# A4988_to_FET_drive.net
KiCad netlist of a schematic drawn in EasyEDA
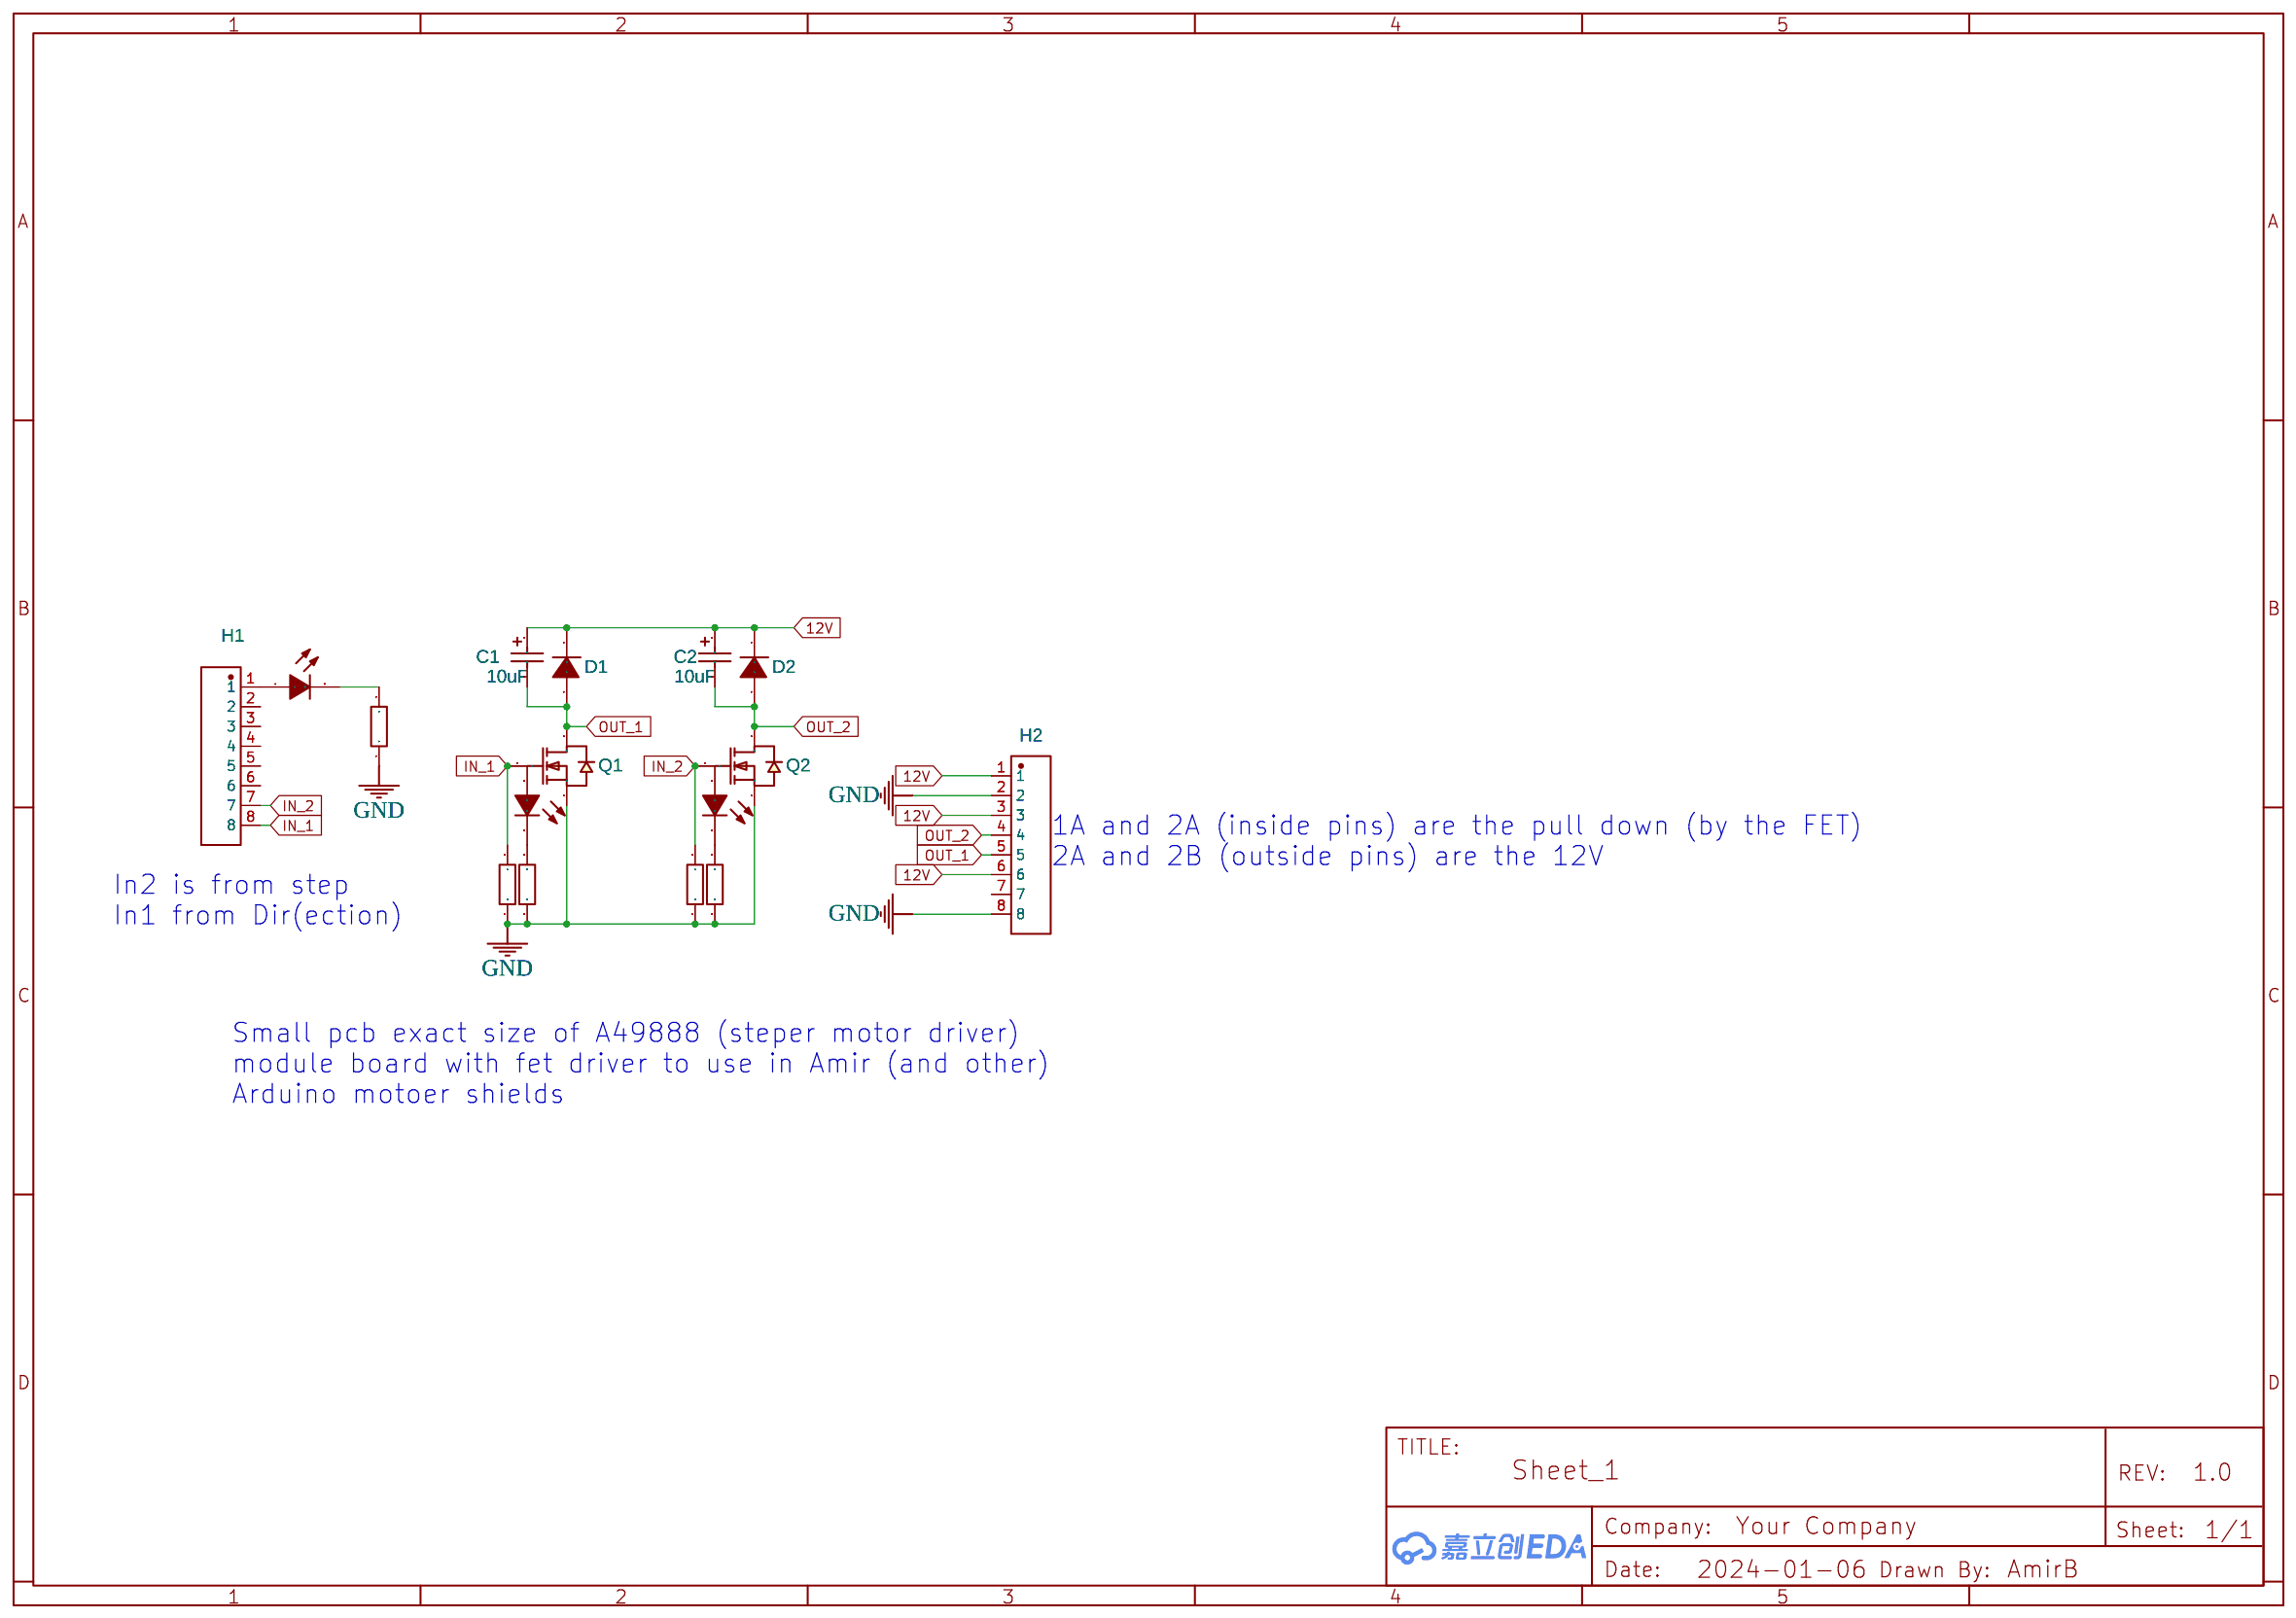
[diagram p0: schematic sheet]

(export (version "E")
  (design (tool "Eeschema 10.0.6"))
  (components
    (comp (ref "C1")
      (value "10uF")
      (fields (field (name "Manufacturer Part") "TAJA106K016RNJ") (field (name "Manufacturer") "Kyocera AVX"))
      (libsource (lib "") (part "TAJA106K016RNJ"))
    )
    (comp (ref "C2")
      (value "10uF")
      (fields (field (name "Manufacturer Part") "TAJA106K016RNJ") (field (name "Manufacturer") "Kyocera AVX"))
      (libsource (lib "") (part "TAJA106K016RNJ"))
    )
    (comp (ref "D1")
      (value "M7_C95872")
      (fields (field (name "Manufacturer Part") "M7") (field (name "Manufacturer") "MDD"))
      (libsource (lib "") (part "M7_C95872"))
    )
    (comp (ref "D2")
      (value "M7_C95872")
      (fields (field (name "Manufacturer Part") "M7") (field (name "Manufacturer") "MDD"))
      (libsource (lib "") (part "M7_C95872"))
    )
    (comp (ref "H1")
      (value "DZ254R-11-08-63")
      (fields (field (name "Manufacturer") "DEALON(德艺隆)"))
      (libsource (lib "") (part "DZ254R-11-08-63_1"))
    )
    (comp (ref "H2")
      (value "DZ254R-11-08-63")
      (fields (field (name "Manufacturer") "DEALON(德艺隆)"))
      (libsource (lib "") (part "DZ254R-11-08-63"))
    )
    (comp (ref "L1")
      (value "LED")
      (fields
        (field (name "BOM_Manufacturer Part") "19-217/BHC-ZL1M2RY/3T")
        (field (name "BOM_Supplier Part") "C72041")
      )
      (libsource (lib "") (part "19-217/BHC-ZL1M2RY/3T_1"))
    )
    (comp (ref "L2")
      (value "LED")
      (fields
        (field (name "BOM_Manufacturer Part") "19-217/BHC-ZL1M2RY/3T")
        (field (name "BOM_Supplier Part") "C72041")
      )
      (libsource (lib "") (part "19-217/BHC-ZL1M2RY/3T_1"))
    )
    (comp (ref "L3")
      (value "LED")
      (fields
        (field (name "BOM_Manufacturer Part") "19-217/BHC-ZL1M2RY/3T")
        (field (name "BOM_Supplier Part") "C72041")
      )
      (libsource (lib "") (part "19-217/BHC-ZL1M2RY/3T"))
    )
    (comp (ref "PR4")
      (value "R10K")
      (fields
        (field (name "BOM_Manufacturer Part") "0603WAF1002T5E")
        (field (name "BOM_Supplier Part") "C25804")
      )
      (libsource (lib "") (part "0603WAF1001T5E_1"))
    )
    (comp (ref "Q1")
      (value "AO3400A")
      (fields (field (name "Manufacturer") "AOS"))
      (libsource (lib "") (part "AO3400A"))
    )
    (comp (ref "Q2")
      (value "AO3400A")
      (fields (field (name "Manufacturer") "AOS"))
      (libsource (lib "") (part "AO3400A"))
    )
    (comp (ref "R2")
      (value "R10K")
      (fields
        (field (name "BOM_Manufacturer Part") "0603WAF1002T5E")
        (field (name "BOM_Supplier Part") "C25804")
      )
      (libsource (lib "") (part "0603WAF1001T5E_2"))
    )
    (comp (ref "RL1")
      (value "R10K")
      (fields
        (field (name "BOM_Manufacturer Part") "0603WAF1002T5E")
        (field (name "BOM_Supplier Part") "C25804")
      )
      (libsource (lib "") (part "0603WAF1001T5E"))
    )
    (comp (ref "RL2")
      (value "R10K")
      (fields
        (field (name "BOM_Manufacturer Part") "0603WAF1002T5E")
        (field (name "BOM_Supplier Part") "C25804")
      )
      (libsource (lib "") (part "0603WAF1001T5E"))
    )
    (comp (ref "RL3")
      (value "R10K")
      (fields
        (field (name "BOM_Manufacturer Part") "0603WAF1002T5E")
        (field (name "BOM_Supplier Part") "C25804")
      )
      (libsource (lib "") (part "0603WAF1001T5E"))
    )
  )
  (nets
    (net (code "1") (name "12V") (class "Default")
      (node (ref "C1") (pin "1") (pinfunction "1_1") (pintype "input"))
      (node (ref "C2") (pin "1") (pinfunction "1_1") (pintype "input"))
      (node (ref "D1") (pin "1") (pinfunction "K_1") (pintype "unspecified"))
      (node (ref "D2") (pin "1") (pinfunction "K_1") (pintype "unspecified"))
      (node (ref "H2") (pin "1") (pinfunction "1_1") (pintype "unspecified"))
      (node (ref "H2") (pin "3") (pinfunction "3_3") (pintype "unspecified"))
      (node (ref "H2") (pin "6") (pinfunction "6_6") (pintype "unspecified"))
    )
    (net (code "2") (name "GND") (class "Default")
      (node (ref "H2") (pin "2") (pinfunction "2_2") (pintype "unspecified"))
      (node (ref "H2") (pin "8") (pinfunction "8_8") (pintype "unspecified"))
      (node (ref "PR4") (pin "1") (pinfunction "1_1") (pintype "input"))
      (node (ref "Q1") (pin "2") (pinfunction "S_2") (pintype "unspecified"))
      (node (ref "Q2") (pin "2") (pinfunction "S_2") (pintype "unspecified"))
      (node (ref "R2") (pin "1") (pinfunction "1_1") (pintype "input"))
      (node (ref "RL1") (pin "1") (pinfunction "1_1") (pintype "input"))
      (node (ref "RL2") (pin "1") (pinfunction "1_1") (pintype "input"))
      (node (ref "RL3") (pin "1") (pinfunction "1_1") (pintype "input"))
    )
    (net (code "3") (name "IN_1") (class "Default")
      (node (ref "H1") (pin "8") (pinfunction "8_8") (pintype "unspecified"))
      (node (ref "L1") (pin "1") (pinfunction "A_1") (pintype "input"))
      (node (ref "PR4") (pin "2") (pinfunction "2_2") (pintype "input"))
      (node (ref "Q1") (pin "1") (pinfunction "G_1") (pintype "unspecified"))
    )
    (net (code "4") (name "IN_2") (class "Default")
      (node (ref "H1") (pin "7") (pinfunction "7_7") (pintype "unspecified"))
      (node (ref "L2") (pin "1") (pinfunction "A_1") (pintype "input"))
      (node (ref "Q2") (pin "1") (pinfunction "G_1") (pintype "unspecified"))
      (node (ref "R2") (pin "2") (pinfunction "2_2") (pintype "input"))
    )
    (net (code "5") (name "Net-(L1-C)") (class "Default")
      (node (ref "L1") (pin "2") (pinfunction "C_2") (pintype "input"))
      (node (ref "RL1") (pin "2") (pinfunction "2_2") (pintype "input"))
    )
    (net (code "6") (name "Net-(L2-C)") (class "Default")
      (node (ref "L2") (pin "2") (pinfunction "C_2") (pintype "input"))
      (node (ref "RL2") (pin "2") (pinfunction "2_2") (pintype "input"))
    )
    (net (code "7") (name "Net-(L3-A)") (class "Default")
      (node (ref "H1") (pin "1") (pinfunction "1_1") (pintype "unspecified"))
      (node (ref "L3") (pin "1") (pinfunction "A_1") (pintype "input"))
    )
    (net (code "8") (name "Net-(L3-C)") (class "Default")
      (node (ref "L3") (pin "2") (pinfunction "C_2") (pintype "input"))
      (node (ref "RL3") (pin "2") (pinfunction "2_2") (pintype "input"))
    )
    (net (code "9") (name "OUT_1") (class "Default")
      (node (ref "C1") (pin "2") (pinfunction "2_2") (pintype "input"))
      (node (ref "D1") (pin "2") (pinfunction "A_2") (pintype "unspecified"))
      (node (ref "H2") (pin "5") (pinfunction "5_5") (pintype "unspecified"))
      (node (ref "Q1") (pin "3") (pinfunction "D_3") (pintype "unspecified"))
    )
    (net (code "10") (name "OUT_2") (class "Default")
      (node (ref "C2") (pin "2") (pinfunction "2_2") (pintype "input"))
      (node (ref "D2") (pin "2") (pinfunction "A_2") (pintype "unspecified"))
      (node (ref "H2") (pin "4") (pinfunction "4_4") (pintype "unspecified"))
      (node (ref "Q2") (pin "3") (pinfunction "D_3") (pintype "unspecified"))
    )
    (net (code "11") (name "unconnected-(H1-Pad2)") (class "Default")
      (node (ref "H1") (pin "2") (pinfunction "2_2") (pintype "unspecified"))
    )
    (net (code "12") (name "unconnected-(H1-Pad3)") (class "Default")
      (node (ref "H1") (pin "3") (pinfunction "3_3") (pintype "unspecified"))
    )
    (net (code "13") (name "unconnected-(H1-Pad4)") (class "Default")
      (node (ref "H1") (pin "4") (pinfunction "4_4") (pintype "unspecified"))
    )
    (net (code "14") (name "unconnected-(H1-Pad5)") (class "Default")
      (node (ref "H1") (pin "5") (pinfunction "5_5") (pintype "unspecified"))
    )
    (net (code "15") (name "unconnected-(H1-Pad6)") (class "Default")
      (node (ref "H1") (pin "6") (pinfunction "6_6") (pintype "unspecified"))
    )
    (net (code "16") (name "unconnected-(H2-Pad7)") (class "Default")
      (node (ref "H2") (pin "7") (pinfunction "7_7") (pintype "unspecified"))
    )
  )
)
